# Supply_Switches_12V_3V3_1V8.net
KiCad netlist of a schematic drawn in Altium Designer
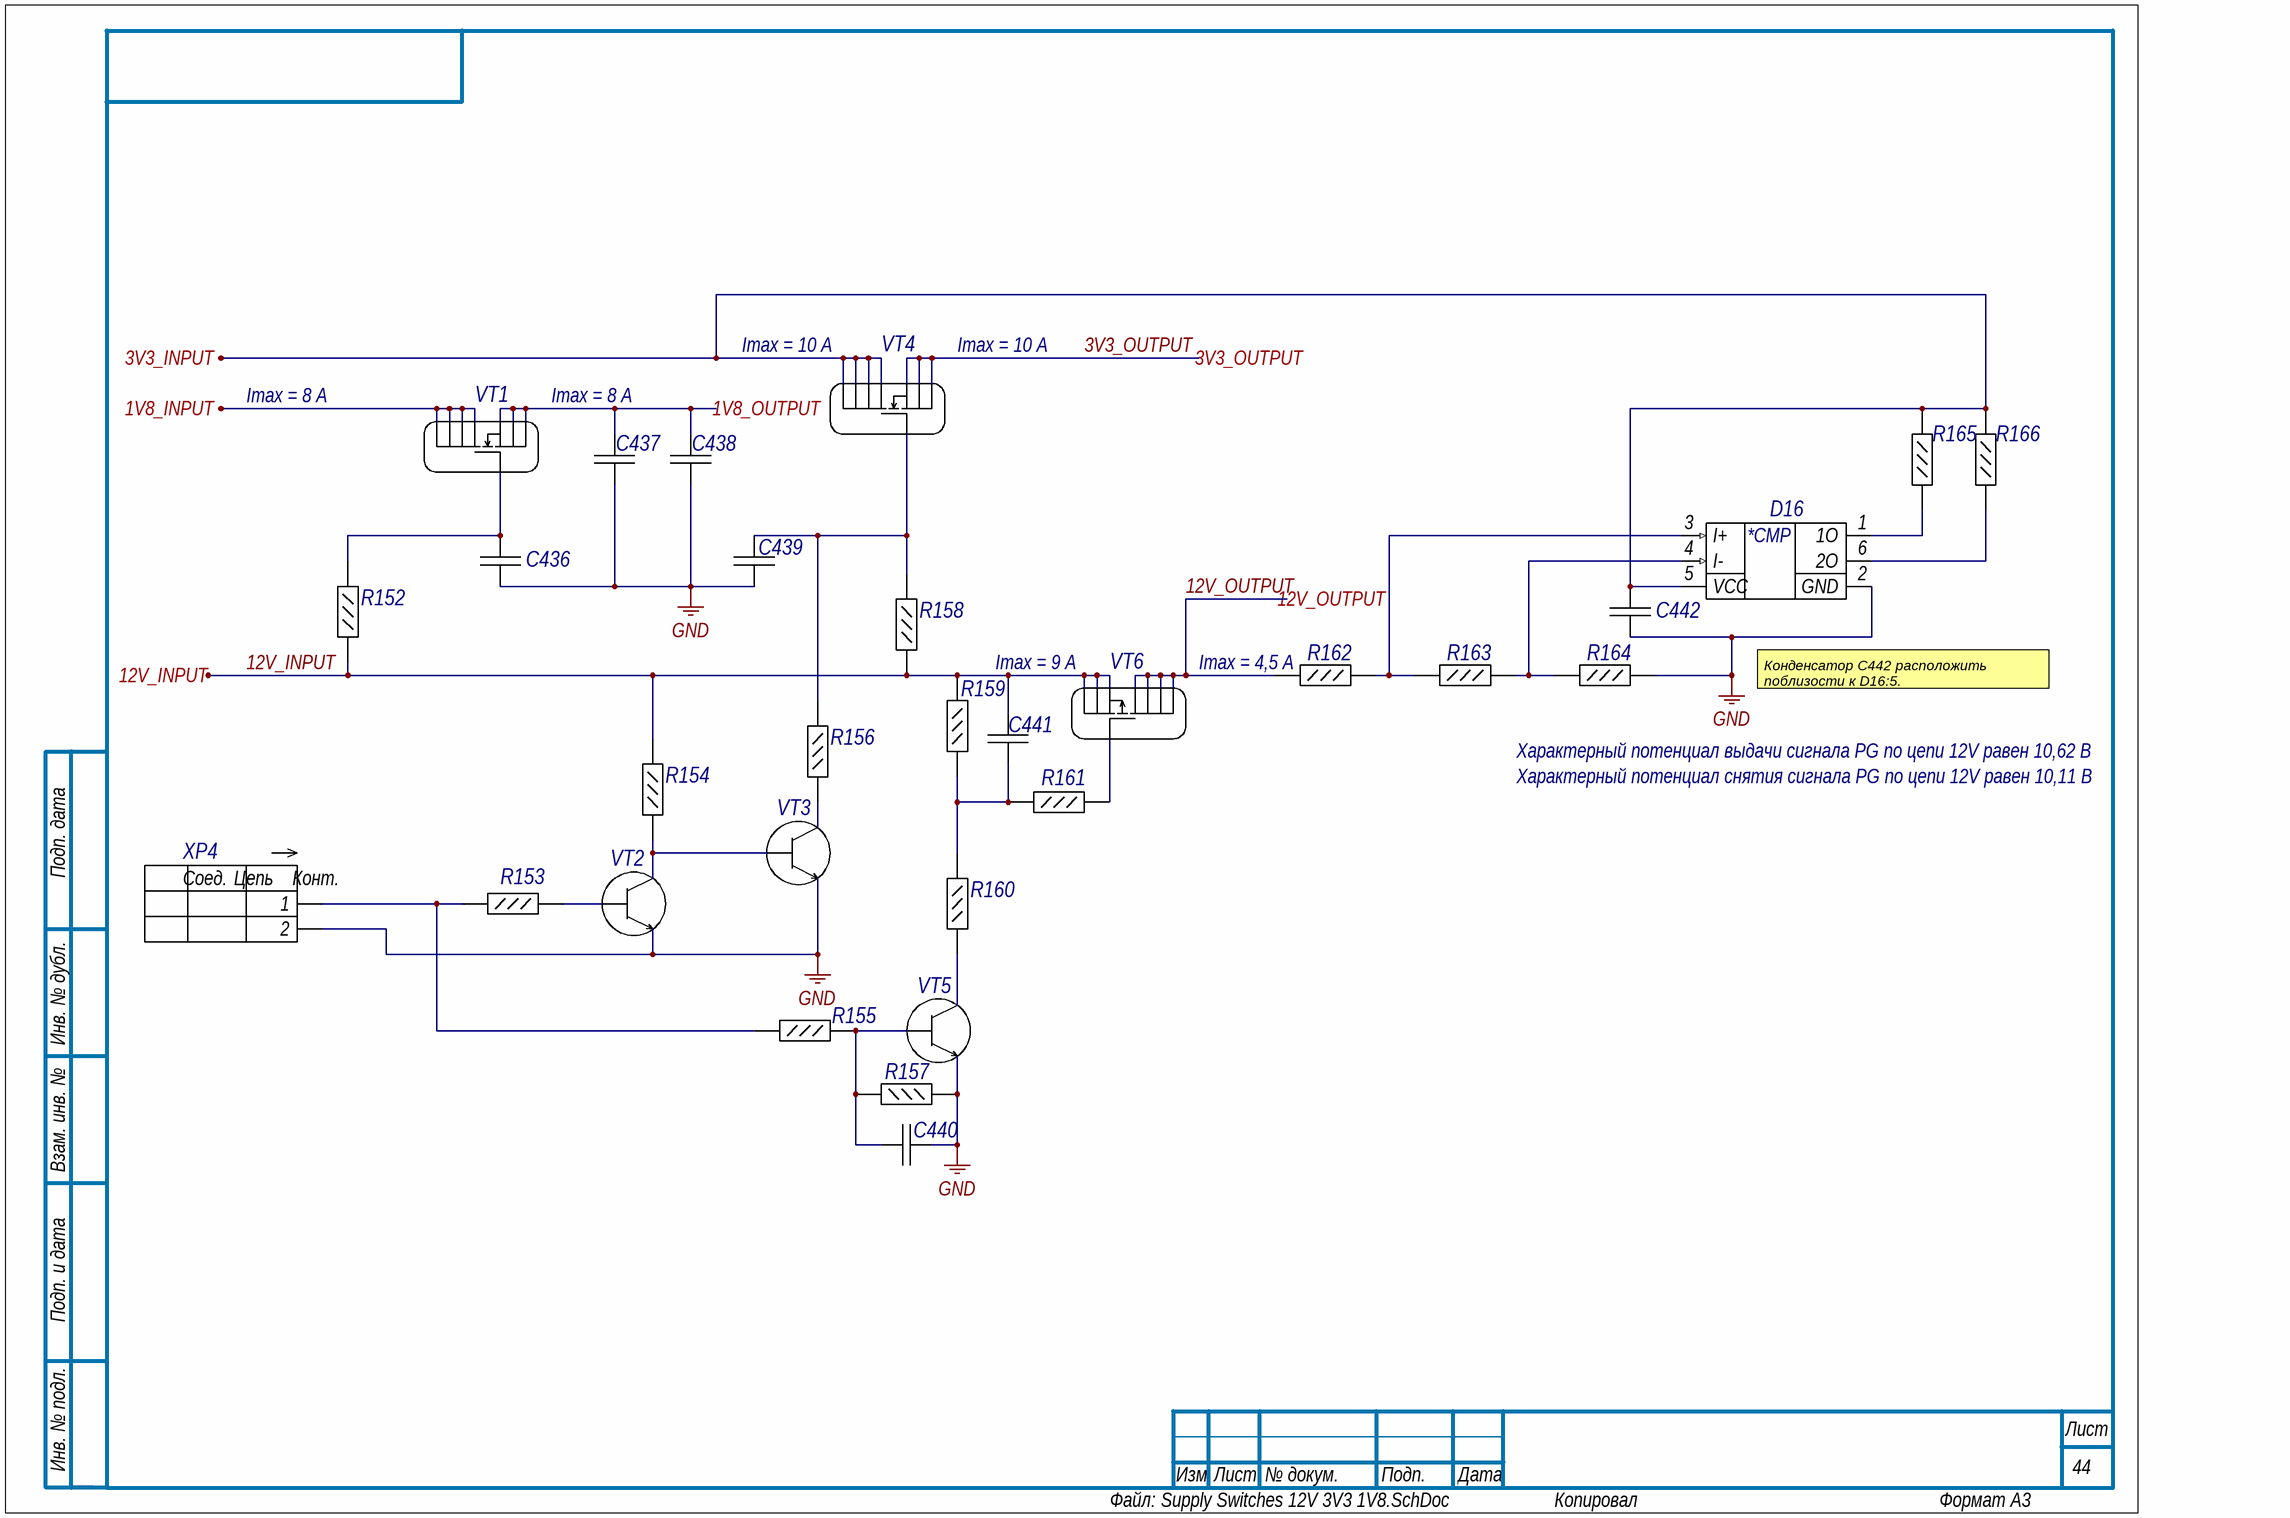
[diagram p0: Supply Switches 12V 3V3 1V8.SchDoc]

(export (version "E")
  (design (tool "Eeschema 10.0.6"))
  (components
    (comp (ref "C436")
      (value "GRM155R71H103KA88D")
      (footprint "CAPC1005X55X25ML05T10")
      (description "Chip Capacitor, 10 nF, +/- 10%, 50 V, -55 to 125 degC, 0402 (1005 Metric), RoHS, Tape and Reel")
      (fields (field (name "TOLERANCE") "10%") (field (name "MANUFACTURER") "Basic Passives"))
      (libsource (lib "MiniPC DB") (part "CAP_NP"))
    )
    (comp (ref "C437")
      (value "C3216X5R1A476M160AB")
      (footprint "CAPC3216X180X20ML20")
      (description "Chip Capacitor, 47 uF, +/- 20%, 10 V, -55 to 85 degC, 1206 (3216 Metric), RoHS, Tape and Reel")
      (fields (field (name "TOLERANCE") "20%"))
      (libsource (lib "MiniPC DB") (part "CAP_NP"))
    )
    (comp (ref "C438")
      (value "C3216X5R1A476M160AB")
      (footprint "CAPC3216X180X20ML20")
      (description "Chip Capacitor, 47 uF, +/- 20%, 10 V, -55 to 85 degC, 1206 (3216 Metric), RoHS, Tape and Reel")
      (fields (field (name "TOLERANCE") "20%"))
      (libsource (lib "MiniPC DB") (part "CAP_NP"))
    )
    (comp (ref "C439")
      (value "GRM155R71H103KA88D")
      (footprint "CAPC1005X55X25ML05T10")
      (description "Chip Capacitor, 10 nF, +/- 10%, 50 V, -55 to 125 degC, 0402 (1005 Metric), RoHS, Tape and Reel")
      (fields (field (name "TOLERANCE") "10%") (field (name "MANUFACTURER") "Basic Passives"))
      (libsource (lib "MiniPC DB") (part "CAP_NP"))
    )
    (comp (ref "C440")
      (value "C1005X7R1E104M")
      (footprint "CAPC1005X55X10LL05")
      (description "Chip Capacitor, 0.1 uF, +/- 20%, 25 V, -55 to 125 degC, 0402 (1005 Metric), RoHS, Tape and Reel")
      (fields (field (name "TOLERANCE") "20%"))
      (libsource (lib "MiniPC DB") (part "CAP_NP"))
    )
    (comp (ref "C441")
      (value "CGB2A1X5R1E105K033BC")
      (footprint "CAPC1005X33X10LL5")
      (description "Chip Capacitor, 1 uF, +/- 10%, 25 V, -55 to 85 degC, 0402 (1005 Metric), RoHS, Tape and Reel")
      (fields (field (name "TOLERANCE") "10%"))
      (libsource (lib "MiniPC DB") (part "CAP_NP"))
    )
    (comp (ref "C442")
      (value "C1005X7R1E104M")
      (footprint "CAPC1005X55X10LL05")
      (description "Chip Capacitor, 0.1 uF, +/- 20%, 25 V, -55 to 125 degC, 0402 (1005 Metric), RoHS, Tape and Reel")
      (fields (field (name "TOLERANCE") "20%"))
      (libsource (lib "MiniPC DB") (part "CAP_NP"))
    )
    (comp (ref "D16")
      (value "TPS3700DDCR")
      (footprint "DDC0006A_M")
      (libsource (lib "MiniPC DB") (part "COMP_DUAL_IU"))
    )
    (comp (ref "R152")
      (value "ERJ-2RKF1003X")
      (footprint "RESC1005X40X25LL05T05")
      (description "Chip Resistor, 100 KOhm, +/- 1%, 100 mW, -55 to 155 degC, 0402 (1005 Metric), RoHS, Tape and Reel")
      (fields (field (name "TOLERANCE") "1%") (field (name "MANUFACTURER") "Basic Passives"))
      (libsource (lib "MiniPC DB") (part "RES-0.05"))
    )
    (comp (ref "R153")
      (value "ERJ-2RKF1002X")
      (footprint "RESC1005X40X25LL05T05")
      (description "Chip Resistor, 10 KOhm, +/- 1%, 100 mW, -55 to 155 degC, 0402 (1005 Metric), RoHS, Tape and Reel")
      (fields (field (name "TOLERANCE") "1%") (field (name "MANUFACTURER") "Basic Passives"))
      (libsource (lib "") (part "RES-0.05_2"))
    )
    (comp (ref "R154")
      (value "ERJ-2RKF1003X")
      (footprint "RESC1005X40X25LL05T05")
      (description "Chip Resistor, 100 KOhm, +/- 1%, 100 mW, -55 to 155 degC, 0402 (1005 Metric), RoHS, Tape and Reel")
      (fields (field (name "TOLERANCE") "1%") (field (name "MANUFACTURER") "Basic Passives"))
      (libsource (lib "MiniPC DB") (part "RES-0.05"))
    )
    (comp (ref "R155")
      (value "ERJ-2RKF1002X")
      (footprint "RESC1005X40X25LL05T05")
      (description "Chip Resistor, 10 KOhm, +/- 1%, 100 mW, -55 to 155 degC, 0402 (1005 Metric), RoHS, Tape and Reel")
      (fields (field (name "TOLERANCE") "1%") (field (name "MANUFACTURER") "Basic Passives"))
      (libsource (lib "") (part "RES-0.05_2"))
    )
    (comp (ref "R156")
      (value "ERJ-2RKF1001X")
      (footprint "RESC1005X40X25LL05T05")
      (description "Chip Resistor, 1 KOhm, +/- 1%, 100 mW, -55 to 155 degC, 0402 (1005 Metric), RoHS, Tape and Reel")
      (fields (field (name "TOLERANCE") "1%") (field (name "MANUFACTURER") "Basic Passives"))
      (libsource (lib "") (part "RES-0.05_1"))
    )
    (comp (ref "R157")
      (value "ERJ-2RKF1002X")
      (footprint "RESC1005X40X25LL05T05")
      (description "Chip Resistor, 10 KOhm, +/- 1%, 100 mW, -55 to 155 degC, 0402 (1005 Metric), RoHS, Tape and Reel")
      (fields (field (name "TOLERANCE") "1%") (field (name "MANUFACTURER") "Basic Passives"))
      (libsource (lib "MiniPC DB") (part "RES-0.05"))
    )
    (comp (ref "R158")
      (value "ERJ-2RKF1003X")
      (footprint "RESC1005X40X25LL05T05")
      (description "Chip Resistor, 100 KOhm, +/- 1%, 100 mW, -55 to 155 degC, 0402 (1005 Metric), RoHS, Tape and Reel")
      (fields (field (name "TOLERANCE") "1%") (field (name "MANUFACTURER") "Basic Passives"))
      (libsource (lib "MiniPC DB") (part "RES-0.05"))
    )
    (comp (ref "R159")
      (value "ERJ-2RKF4992X")
      (footprint "RESC1005X40X25LL05T05")
      (description "Chip Resistor, 49.9 KOhm, +/- 1%, 100 mW, -55 to 155 degC, 0402 (1005 Metric), RoHS, Tape and Reel")
      (fields (field (name "TOLERANCE") "1%") (field (name "MANUFACTURER") "Basic Passives"))
      (libsource (lib "") (part "RES-0.05_1"))
    )
    (comp (ref "R160")
      (value "ERJ-2RKF1003X")
      (footprint "RESC1005X40X25LL05T05")
      (description "Chip Resistor, 100 KOhm, +/- 1%, 100 mW, -55 to 155 degC, 0402 (1005 Metric), RoHS, Tape and Reel")
      (fields (field (name "TOLERANCE") "1%") (field (name "MANUFACTURER") "Basic Passives"))
      (libsource (lib "") (part "RES-0.05_1"))
    )
    (comp (ref "R161")
      (value "ERJ-2RKF10R0X")
      (footprint "RESC1005X40X25LL05T05")
      (description "Chip Resistor, 10 Ohm, +/- 1%, 100 mW, -55 to 155 degC, 0402 (1005 Metric), RoHS, Tape and Reel")
      (fields (field (name "TOLERANCE") "1%") (field (name "MANUFACTURER") "Basic Passives"))
      (libsource (lib "") (part "RES-0.05_1"))
    )
    (comp (ref "R162")
      (value "ERJ-2RKF2552x")
      (footprint "RESC1005X40X25LL05T05")
      (description "Chip Resistor, 25.5 KOhm, +/- 1%, 100 mW, -55 to 155 degC, 0402 (1005 Metric), RoHS, Tape and Reel")
      (fields (field (name "TOLERANCE") "1%"))
      (libsource (lib "") (part "RES-0.05_2"))
    )
    (comp (ref "R163")
      (value "NRC04F49R9TRF")
      (footprint "RESC1005X35X25NL8T10")
      (description "Chip Resistor, 49.9 Ohm, +/- 1%, 0.06 W, -55 to 155 degC, 0402 (1005 Metric), RoHS, Tape and Reel")
      (fields (field (name "TOLERANCE") "1%"))
      (libsource (lib "") (part "RES-0.05_2"))
    )
    (comp (ref "R164")
      (value "ERJ-2RKF1001X")
      (footprint "RESC1005X40X25LL05T05")
      (description "Chip Resistor, 1 KOhm, +/- 1%, 100 mW, -55 to 155 degC, 0402 (1005 Metric), RoHS, Tape and Reel")
      (fields (field (name "TOLERANCE") "1%") (field (name "MANUFACTURER") "Basic Passives"))
      (libsource (lib "") (part "RES-0.05_2"))
    )
    (comp (ref "R165")
      (value "ERJ-2RKF1002X")
      (footprint "RESC1005X40X25LL05T05")
      (description "Chip Resistor, 10 KOhm, +/- 1%, 100 mW, -55 to 155 degC, 0402 (1005 Metric), RoHS, Tape and Reel")
      (fields (field (name "TOLERANCE") "1%") (field (name "MANUFACTURER") "Basic Passives"))
      (libsource (lib "MiniPC DB") (part "RES-0.05"))
    )
    (comp (ref "R166")
      (value "ERJ-2RKF1002X")
      (footprint "RESC1005X40X25LL05T05")
      (description "Chip Resistor, 10 KOhm, +/- 1%, 100 mW, -55 to 155 degC, 0402 (1005 Metric), RoHS, Tape and Reel")
      (fields (field (name "TOLERANCE") "1%") (field (name "MANUFACTURER") "Basic Passives"))
      (libsource (lib "MiniPC DB") (part "RES-0.05"))
    )
    (comp (ref "VT1")
      (value "SiRA00DP-T1-GE3")
      (footprint "VISH-PPAKSO-8_V")
      (description "N-Channe MOSFET, 30 V, -55 to 150 degC, 8-Pin SMD (PPAKSO-8), RoHS, Tape and Reel")
      (libsource (lib "MiniPC DB") (part "MOSFET-N-IND_2"))
    )
    (comp (ref "VT2")
      (value "MMBT2222A-7-F")
      (footprint "DIOD-SOT23-3_V")
      (description "NPN Small Signal Transistor, 40 V, -55 to 150 degC, 3-Pin SOT23, RoHS, Tape and Reel")
      (fields (field (name "MANUFACTURER") "Diodes Inc"))
      (libsource (lib "MiniPC DB") (part "BJT-NPN-BEC"))
    )
    (comp (ref "VT3")
      (value "MMBT2222A-7-F")
      (footprint "DIOD-SOT23-3_V")
      (description "NPN Small Signal Transistor, 40 V, -55 to 150 degC, 3-Pin SOT23, RoHS, Tape and Reel")
      (fields (field (name "MANUFACTURER") "Diodes Inc"))
      (libsource (lib "") (part "BJT-NPN-BEC_1"))
    )
    (comp (ref "VT4")
      (value "SiRA00DP-T1-GE3")
      (footprint "VISH-PPAKSO-8_V")
      (description "N-Channe MOSFET, 30 V, -55 to 150 degC, 8-Pin SMD (PPAKSO-8), RoHS, Tape and Reel")
      (libsource (lib "MiniPC DB") (part "MOSFET-N-IND_2"))
    )
    (comp (ref "VT5")
      (value "MMBT2222A-7-F")
      (footprint "DIOD-SOT23-3_V")
      (description "NPN Small Signal Transistor, 40 V, -55 to 150 degC, 3-Pin SOT23, RoHS, Tape and Reel")
      (fields (field (name "MANUFACTURER") "Diodes Inc"))
      (libsource (lib "MiniPC DB") (part "BJT-NPN-BEC"))
    )
    (comp (ref "VT6")
      (value "Si7635DP-T1-GE3")
      (footprint "VISH-PPAKSO-8_V")
      (description "P-Channel MOSFET, 20 V, -55 to 150 degC, 8-Pin SMD (PPAKSO-8), RoHS, Tape and Reel")
      (libsource (lib "MiniPC DB") (part "MOSFET-P-IND_2"))
    )
    (comp (ref "XP4")
      (value "613 002 111 21")
      (footprint "WE-61300211121_V")
      (fields (field (name "MANUFACTURER") "Wuerth Elektronik"))
      (libsource (lib "MiniPC DB") (part "VILKA_2K"))
    )
  )
  (nets
    (net (code "1") (name "/1V8_INPUT") (class "Default")
      (node (ref "VT1") (pin "5") (pinfunction "D_5") (pintype "passive"))
      (node (ref "VT1") (pin "6") (pinfunction "D_6") (pintype "passive"))
      (node (ref "VT1") (pin "7") (pinfunction "D_7") (pintype "passive"))
      (node (ref "VT1") (pin "8") (pinfunction "D_8") (pintype "passive"))
    )
    (net (code "2") (name "/1V8_OUTPUT") (class "Default")
      (node (ref "C437") (pin "2") (pinfunction "2_2") (pintype "passive"))
      (node (ref "C438") (pin "2") (pinfunction "2_2") (pintype "passive"))
      (node (ref "VT1") (pin "1") (pinfunction "S_1") (pintype "passive"))
      (node (ref "VT1") (pin "2") (pinfunction "S_2") (pintype "passive"))
      (node (ref "VT1") (pin "3") (pinfunction "S_3") (pintype "passive"))
    )
    (net (code "3") (name "/3V3_INPUT") (class "Default")
      (node (ref "C442") (pin "2") (pinfunction "2_2") (pintype "passive"))
      (node (ref "D16") (pin "5") (pinfunction "VCC_5") (pintype "passive"))
      (node (ref "R165") (pin "1") (pinfunction "1_1") (pintype "passive"))
      (node (ref "R166") (pin "1") (pinfunction "1_1") (pintype "passive"))
      (node (ref "VT4") (pin "5") (pinfunction "D_5") (pintype "passive"))
      (node (ref "VT4") (pin "6") (pinfunction "D_6") (pintype "passive"))
      (node (ref "VT4") (pin "7") (pinfunction "D_7") (pintype "passive"))
      (node (ref "VT4") (pin "8") (pinfunction "D_8") (pintype "passive"))
    )
    (net (code "4") (name "/3V3_OUTPUT") (class "Default")
      (node (ref "VT4") (pin "1") (pinfunction "S_1") (pintype "passive"))
      (node (ref "VT4") (pin "2") (pinfunction "S_2") (pintype "passive"))
      (node (ref "VT4") (pin "3") (pinfunction "S_3") (pintype "passive"))
    )
    (net (code "5") (name "/12V_INPUT") (class "Default")
      (node (ref "C441") (pin "2") (pinfunction "2_2") (pintype "passive"))
      (node (ref "R152") (pin "2") (pinfunction "2_2") (pintype "passive"))
      (node (ref "R154") (pin "1") (pinfunction "1_1") (pintype "passive"))
      (node (ref "R158") (pin "2") (pinfunction "2_2") (pintype "passive"))
      (node (ref "R159") (pin "2") (pinfunction "2_2") (pintype "passive"))
      (node (ref "VT6") (pin "1") (pinfunction "S_1") (pintype "passive"))
      (node (ref "VT6") (pin "2") (pinfunction "S_2") (pintype "passive"))
      (node (ref "VT6") (pin "3") (pinfunction "S_3") (pintype "passive"))
    )
    (net (code "6") (name "/12V_OUTPUT") (class "Default")
      (node (ref "R162") (pin "2") (pinfunction "2_2") (pintype "passive"))
      (node (ref "VT6") (pin "5") (pinfunction "D_5") (pintype "passive"))
      (node (ref "VT6") (pin "6") (pinfunction "D_6") (pintype "passive"))
      (node (ref "VT6") (pin "7") (pinfunction "D_7") (pintype "passive"))
      (node (ref "VT6") (pin "8") (pinfunction "D_8") (pintype "passive"))
    )
    (net (code "7") (name "GND") (class "Default")
      (node (ref "C436") (pin "1") (pinfunction "1_1") (pintype "passive"))
      (node (ref "C437") (pin "1") (pinfunction "1_1") (pintype "passive"))
      (node (ref "C438") (pin "1") (pinfunction "1_1") (pintype "passive"))
      (node (ref "C439") (pin "1") (pinfunction "1_1") (pintype "passive"))
      (node (ref "C440") (pin "1") (pinfunction "1_1") (pintype "passive"))
      (node (ref "C442") (pin "1") (pinfunction "1_1") (pintype "passive"))
      (node (ref "D16") (pin "2") (pinfunction "GND_2") (pintype "passive"))
      (node (ref "R157") (pin "1") (pinfunction "1_1") (pintype "passive"))
      (node (ref "R164") (pin "1") (pinfunction "1_1") (pintype "passive"))
      (node (ref "VT2") (pin "2") (pinfunction "2_2") (pintype "passive"))
      (node (ref "VT3") (pin "2") (pinfunction "2_2") (pintype "passive"))
      (node (ref "VT5") (pin "2") (pinfunction "2_2") (pintype "passive"))
      (node (ref "XP4") (pin "2") (pinfunction "2_2") (pintype "passive"))
    )
    (net (code "8") (name "Net-(C440-Pad2)") (class "Default")
      (node (ref "C440") (pin "2") (pinfunction "2_2") (pintype "passive"))
      (node (ref "R155") (pin "1") (pinfunction "1_1") (pintype "passive"))
      (node (ref "R157") (pin "2") (pinfunction "2_2") (pintype "passive"))
      (node (ref "VT5") (pin "1") (pinfunction "1_1") (pintype "passive"))
    )
    (net (code "9") (name "Net-(C441-Pad1)") (class "Default")
      (node (ref "C441") (pin "1") (pinfunction "1_1") (pintype "passive"))
      (node (ref "R159") (pin "1") (pinfunction "1_1") (pintype "passive"))
      (node (ref "R160") (pin "2") (pinfunction "2_2") (pintype "passive"))
      (node (ref "R161") (pin "1") (pinfunction "1_1") (pintype "passive"))
    )
    (net (code "10") (name "Net-(D16-1O)") (class "Default")
      (node (ref "D16") (pin "1") (pinfunction "1O_1") (pintype "open_collector"))
      (node (ref "R165") (pin "2") (pinfunction "2_2") (pintype "passive"))
    )
    (net (code "11") (name "Net-(D16-2O)") (class "Default")
      (node (ref "D16") (pin "6") (pinfunction "2O_6") (pintype "open_collector"))
      (node (ref "R166") (pin "2") (pinfunction "2_2") (pintype "passive"))
    )
    (net (code "12") (name "Net-(D16-I+)") (class "Default")
      (node (ref "D16") (pin "3") (pinfunction "I+_3") (pintype "input"))
      (node (ref "R162") (pin "1") (pinfunction "1_1") (pintype "passive"))
      (node (ref "R163") (pin "2") (pinfunction "2_2") (pintype "passive"))
    )
    (net (code "13") (name "Net-(D16-I-)") (class "Default")
      (node (ref "D16") (pin "4") (pinfunction "I-_4") (pintype "input"))
      (node (ref "R163") (pin "1") (pinfunction "1_1") (pintype "passive"))
      (node (ref "R164") (pin "2") (pinfunction "2_2") (pintype "passive"))
    )
    (net (code "14") (name "Net-(R153-Pad1)") (class "Default")
      (node (ref "R153") (pin "1") (pinfunction "1_1") (pintype "passive"))
      (node (ref "VT2") (pin "1") (pinfunction "1_1") (pintype "passive"))
    )
    (net (code "15") (name "Net-(R153-Pad2)") (class "Default")
      (node (ref "R153") (pin "2") (pinfunction "2_2") (pintype "passive"))
      (node (ref "R155") (pin "2") (pinfunction "2_2") (pintype "passive"))
      (node (ref "XP4") (pin "1") (pinfunction "1_1") (pintype "passive"))
    )
    (net (code "16") (name "Net-(R154-Pad2)") (class "Default")
      (node (ref "R154") (pin "2") (pinfunction "2_2") (pintype "passive"))
      (node (ref "VT2") (pin "3") (pinfunction "3_3") (pintype "passive"))
      (node (ref "VT3") (pin "1") (pinfunction "1_1") (pintype "passive"))
    )
    (net (code "17") (name "Net-(R156-Pad1)") (class "Default")
      (node (ref "R156") (pin "1") (pinfunction "1_1") (pintype "passive"))
      (node (ref "VT3") (pin "3") (pinfunction "3_3") (pintype "passive"))
    )
    (net (code "18") (name "Net-(R160-Pad1)") (class "Default")
      (node (ref "R160") (pin "1") (pinfunction "1_1") (pintype "passive"))
      (node (ref "VT5") (pin "3") (pinfunction "3_3") (pintype "passive"))
    )
    (net (code "19") (name "Net-(VT1-G)") (class "Default")
      (node (ref "C436") (pin "2") (pinfunction "2_2") (pintype "passive"))
      (node (ref "R152") (pin "1") (pinfunction "1_1") (pintype "passive"))
      (node (ref "VT1") (pin "4") (pinfunction "G_4") (pintype "passive"))
    )
    (net (code "20") (name "Net-(VT4-G)") (class "Default")
      (node (ref "C439") (pin "2") (pinfunction "2_2") (pintype "passive"))
      (node (ref "R156") (pin "2") (pinfunction "2_2") (pintype "passive"))
      (node (ref "R158") (pin "1") (pinfunction "1_1") (pintype "passive"))
      (node (ref "VT4") (pin "4") (pinfunction "G_4") (pintype "passive"))
    )
    (net (code "21") (name "Net-(VT6-G)") (class "Default")
      (node (ref "R161") (pin "2") (pinfunction "2_2") (pintype "passive"))
      (node (ref "VT6") (pin "4") (pinfunction "G_4") (pintype "passive"))
    )
  )
)
